# PowerSupply.net
KiCad netlist of a schematic drawn in Altium Designer
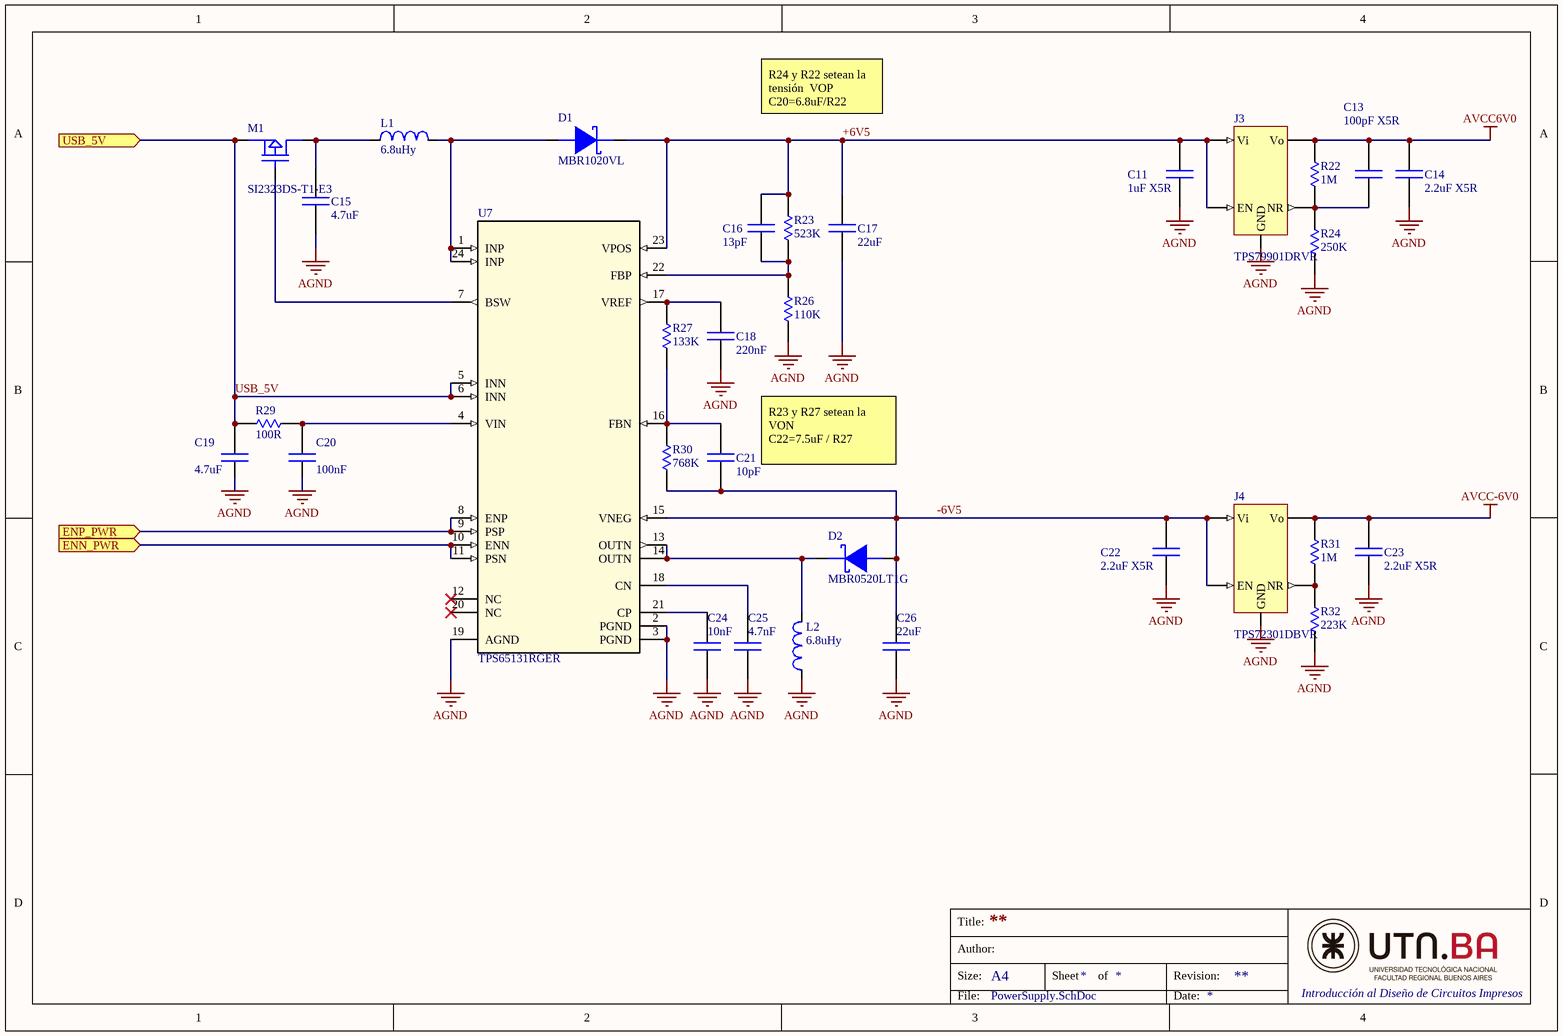
[diagram p0: PowerSupply.SchDoc]

(export (version "E")
  (design (tool "Eeschema 10.0.6"))
  (components
    (comp (ref "C11")
      (value "1uF X5R")
      (footprint "C_0805")
      (description "Capacitor")
      (libsource (lib "Gen_func") (part "Cap"))
    )
    (comp (ref "C13")
      (value "100pF X5R")
      (footprint "C_0805")
      (description "Capacitor")
      (libsource (lib "Gen_func") (part "Cap"))
    )
    (comp (ref "C14")
      (value "2.2uF X5R")
      (footprint "C_0805")
      (description "Capacitor")
      (libsource (lib "Gen_func") (part "Cap"))
    )
    (comp (ref "C15")
      (value "4.7uF")
      (footprint "C_0805")
      (description "Capacitor")
      (libsource (lib "Gen_func") (part "Cap"))
    )
    (comp (ref "C16")
      (value "13pF")
      (footprint "C_0603")
      (description "Capacitor")
      (libsource (lib "Gen_func") (part "Cap"))
    )
    (comp (ref "C17")
      (value "22uF")
      (footprint "C_1206")
      (description "Capacitor")
      (libsource (lib "Gen_func") (part "Cap"))
    )
    (comp (ref "C18")
      (value "220nF")
      (footprint "C_0603")
      (description "Capacitor")
      (libsource (lib "Gen_func") (part "Cap"))
    )
    (comp (ref "C19")
      (value "4.7uF")
      (footprint "C_0805")
      (description "Capacitor")
      (libsource (lib "Gen_func") (part "Cap"))
    )
    (comp (ref "C20")
      (value "100nF")
      (footprint "C_0603")
      (description "Capacitor")
      (libsource (lib "Gen_func") (part "Cap"))
    )
    (comp (ref "C21")
      (value "10pF")
      (footprint "C_0603")
      (description "Capacitor")
      (libsource (lib "Gen_func") (part "Cap"))
    )
    (comp (ref "C22")
      (value "2.2uF X5R")
      (footprint "C_0805")
      (description "Capacitor")
      (libsource (lib "Gen_func") (part "Cap"))
    )
    (comp (ref "C23")
      (value "2.2uF X5R")
      (footprint "C_0805")
      (description "Capacitor")
      (libsource (lib "Gen_func") (part "Cap"))
    )
    (comp (ref "C24")
      (value "10nF")
      (footprint "C_0603")
      (description "Capacitor")
      (libsource (lib "Gen_func") (part "Cap"))
    )
    (comp (ref "C25")
      (value "4.7nF")
      (footprint "C_0603")
      (description "Capacitor")
      (libsource (lib "Gen_func") (part "Cap"))
    )
    (comp (ref "C26")
      (value "22uF")
      (footprint "C_1206")
      (description "Capacitor")
      (libsource (lib "Gen_func") (part "Cap"))
    )
    (comp (ref "D1")
      (value "MBR1020VL")
      (footprint "SOD-123")
      (description "Schottky diode")
      (libsource (lib "Gen_func") (part "Diode"))
    )
    (comp (ref "D2")
      (value "MBR0520LT1G")
      (footprint "SOD-123")
      (description "Schottky diode")
      (libsource (lib "Gen_func") (part "Diode"))
    )
    (comp (ref "J3")
      (value "TPS79901DRVR")
      (footprint "WSON")
      (description "LDO_Adjustable")
      (libsource (lib "Gen_func") (part "LDO"))
    )
    (comp (ref "J4")
      (value "TPS72301DBVR")
      (footprint "SOT_23")
      (description "LDO_Adjustable")
      (libsource (lib "Gen_func") (part "LDO"))
    )
    (comp (ref "L1")
      (value "6.8uHy")
      (footprint "L_4028")
      (description "Inductor")
      (libsource (lib "Gen_func") (part "Ind"))
    )
    (comp (ref "L2")
      (value "6.8uHy")
      (footprint "L_4028")
      (description "Inductor")
      (libsource (lib "Gen_func") (part "Ind"))
    )
    (comp (ref "M1")
      (value "SI2323DS-T1-E3")
      (footprint "SOT_23_Q")
      (description "Transistor")
      (libsource (lib "Gen_func") (part "PMOS"))
    )
    (comp (ref "R22")
      (value "1M")
      (footprint "R_0603")
      (description "Resistor")
      (libsource (lib "Gen_func") (part "Res"))
    )
    (comp (ref "R23")
      (value "523K")
      (footprint "R_0603")
      (description "Resistor")
      (libsource (lib "Gen_func") (part "Res"))
    )
    (comp (ref "R24")
      (value "250K")
      (footprint "R_0603")
      (description "Resistor")
      (libsource (lib "Gen_func") (part "Res"))
    )
    (comp (ref "R26")
      (value "110K")
      (footprint "R_0603")
      (description "Resistor")
      (libsource (lib "Gen_func") (part "Res"))
    )
    (comp (ref "R27")
      (value "133K")
      (footprint "R_0603")
      (description "Resistor")
      (libsource (lib "Gen_func") (part "Res"))
    )
    (comp (ref "R29")
      (value "100R")
      (footprint "R_0603")
      (description "Resistor")
      (libsource (lib "Gen_func") (part "Res"))
    )
    (comp (ref "R30")
      (value "768K")
      (footprint "R_0603")
      (description "Resistor")
      (libsource (lib "Gen_func") (part "Res"))
    )
    (comp (ref "R31")
      (value "1M")
      (footprint "R_0603")
      (description "Resistor")
      (libsource (lib "Gen_func") (part "Res"))
    )
    (comp (ref "R32")
      (value "223K")
      (footprint "R_0603")
      (description "Resistor")
      (libsource (lib "Gen_func") (part "Res"))
    )
    (comp (ref "U7")
      (value "TPS65131RGER")
      (footprint "VQFN-N24")
      (description "Positive and Negative Output DC-DC Converter")
      (libsource (lib "Gen_func") (part "TPS65131RGER"))
    )
  )
  (nets
    (net (code "1") (name "/+6V5") (class "Default")
      (node (ref "C11") (pin "1") (pinfunction "1_1") (pintype "passive"))
      (node (ref "C16") (pin "2") (pinfunction "2_2") (pintype "passive"))
      (node (ref "C17") (pin "2") (pinfunction "2_2") (pintype "passive"))
      (node (ref "D1") (pin "1") (pinfunction "K_1") (pintype "passive"))
      (node (ref "J3") (pin "1") (pinfunction "Vi_1") (pintype "input"))
      (node (ref "J3") (pin "3") (pinfunction "EN_3") (pintype "input"))
      (node (ref "R23") (pin "1") (pinfunction "1_1") (pintype "passive"))
      (node (ref "U7") (pin "23") (pinfunction "VPOS_23") (pintype "input"))
    )
    (net (code "2") (name "/-6V5") (class "Default")
      (node (ref "C21") (pin "1") (pinfunction "1_1") (pintype "passive"))
      (node (ref "C22") (pin "1") (pinfunction "1_1") (pintype "passive"))
      (node (ref "C26") (pin "1") (pinfunction "1_1") (pintype "passive"))
      (node (ref "D2") (pin "2") (pinfunction "A_2") (pintype "passive"))
      (node (ref "J4") (pin "1") (pinfunction "Vi_1") (pintype "input"))
      (node (ref "J4") (pin "3") (pinfunction "EN_3") (pintype "input"))
      (node (ref "R30") (pin "2") (pinfunction "2_2") (pintype "passive"))
      (node (ref "U7") (pin "15") (pinfunction "VNEG_15") (pintype "input"))
    )
    (net (code "3") (name "/ENN_PWR") (class "Default")
      (node (ref "U7") (pin "10") (pinfunction "ENN_10") (pintype "input"))
      (node (ref "U7") (pin "11") (pinfunction "PSN_11") (pintype "input"))
    )
    (net (code "4") (name "/ENP_PWR") (class "Default")
      (node (ref "U7") (pin "8") (pinfunction "ENP_8") (pintype "input"))
      (node (ref "U7") (pin "9") (pinfunction "PSP_9") (pintype "input"))
    )
    (net (code "5") (name "/USB_5V") (class "Default")
      (node (ref "C19") (pin "1") (pinfunction "1_1") (pintype "passive"))
      (node (ref "M1") (pin "2") (pinfunction "Source_2") (pintype "passive"))
      (node (ref "R29") (pin "1") (pinfunction "1_1") (pintype "passive"))
      (node (ref "U7") (pin "5") (pinfunction "INN_5") (pintype "input"))
      (node (ref "U7") (pin "6") (pinfunction "INN_6") (pintype "input"))
    )
    (net (code "6") (name "AGND") (class "Default")
      (node (ref "C11") (pin "2") (pinfunction "2_2") (pintype "passive"))
      (node (ref "C14") (pin "2") (pinfunction "2_2") (pintype "passive"))
      (node (ref "C15") (pin "2") (pinfunction "2_2") (pintype "passive"))
      (node (ref "C17") (pin "1") (pinfunction "1_1") (pintype "passive"))
      (node (ref "C18") (pin "2") (pinfunction "2_2") (pintype "passive"))
      (node (ref "C19") (pin "2") (pinfunction "2_2") (pintype "passive"))
      (node (ref "C20") (pin "2") (pinfunction "2_2") (pintype "passive"))
      (node (ref "C22") (pin "2") (pinfunction "2_2") (pintype "passive"))
      (node (ref "C23") (pin "2") (pinfunction "2_2") (pintype "passive"))
      (node (ref "C24") (pin "2") (pinfunction "2_2") (pintype "passive"))
      (node (ref "C25") (pin "2") (pinfunction "2_2") (pintype "passive"))
      (node (ref "C26") (pin "2") (pinfunction "2_2") (pintype "passive"))
      (node (ref "J3") (pin "2") (pinfunction "GND_2") (pintype "power_in"))
      (node (ref "J4") (pin "2") (pinfunction "GND_2") (pintype "power_in"))
      (node (ref "L2") (pin "1") (pinfunction "1_1") (pintype "passive"))
      (node (ref "R24") (pin "1") (pinfunction "1_1") (pintype "passive"))
      (node (ref "R26") (pin "2") (pinfunction "2_2") (pintype "passive"))
      (node (ref "R32") (pin "1") (pinfunction "1_1") (pintype "passive"))
      (node (ref "U7") (pin "19") (pinfunction "AGND_19") (pintype "power_in"))
      (node (ref "U7") (pin "2") (pinfunction "PGND_2") (pintype "power_in"))
      (node (ref "U7") (pin "3") (pinfunction "PGND_3") (pintype "power_in"))
    )
    (net (code "7") (name "AVCC-6V0") (class "Default")
      (node (ref "C23") (pin "1") (pinfunction "1_1") (pintype "passive"))
      (node (ref "J4") (pin "5") (pinfunction "Vo_5") (pintype "power_in"))
      (node (ref "R31") (pin "2") (pinfunction "2_2") (pintype "passive"))
    )
    (net (code "8") (name "AVCC6V0") (class "Default")
      (node (ref "C13") (pin "1") (pinfunction "1_1") (pintype "passive"))
      (node (ref "C14") (pin "1") (pinfunction "1_1") (pintype "passive"))
      (node (ref "J3") (pin "5") (pinfunction "Vo_5") (pintype "power_in"))
      (node (ref "R22") (pin "2") (pinfunction "2_2") (pintype "passive"))
    )
    (net (code "9") (name "Net-(D1-A)") (class "Default")
      (node (ref "D1") (pin "2") (pinfunction "A_2") (pintype "passive"))
      (node (ref "L1") (pin "2") (pinfunction "2_2") (pintype "passive"))
      (node (ref "U7") (pin "1") (pinfunction "INP_1") (pintype "input"))
      (node (ref "U7") (pin "24") (pinfunction "INP_24") (pintype "input"))
    )
    (net (code "10") (name "Net-(D2-K)") (class "Default")
      (node (ref "D2") (pin "1") (pinfunction "K_1") (pintype "passive"))
      (node (ref "L2") (pin "2") (pinfunction "2_2") (pintype "passive"))
      (node (ref "U7") (pin "13") (pinfunction "OUTN_13") (pintype "output"))
      (node (ref "U7") (pin "14") (pinfunction "OUTN_14") (pintype "passive"))
    )
    (net (code "11") (name "Net-(J3-NR)") (class "Default")
      (node (ref "C13") (pin "2") (pinfunction "2_2") (pintype "passive"))
      (node (ref "J3") (pin "4") (pinfunction "NR_4") (pintype "output"))
      (node (ref "R22") (pin "1") (pinfunction "1_1") (pintype "passive"))
      (node (ref "R24") (pin "2") (pinfunction "2_2") (pintype "passive"))
    )
    (net (code "12") (name "Net-(J4-NR)") (class "Default")
      (node (ref "J4") (pin "4") (pinfunction "NR_4") (pintype "output"))
      (node (ref "R31") (pin "1") (pinfunction "1_1") (pintype "passive"))
      (node (ref "R32") (pin "2") (pinfunction "2_2") (pintype "passive"))
    )
    (net (code "13") (name "Net-(M1-Drain)") (class "Default")
      (node (ref "C15") (pin "1") (pinfunction "1_1") (pintype "passive"))
      (node (ref "L1") (pin "1") (pinfunction "1_1") (pintype "passive"))
      (node (ref "M1") (pin "3") (pinfunction "Drain_3") (pintype "passive"))
    )
    (net (code "14") (name "Net-(M1-Gate)") (class "Default")
      (node (ref "M1") (pin "1") (pinfunction "Gate_1") (pintype "passive"))
      (node (ref "U7") (pin "7") (pinfunction "BSW_7") (pintype "output"))
    )
    (net (code "15") (name "Net-(U7-CN)") (class "Default")
      (node (ref "C25") (pin "1") (pinfunction "1_1") (pintype "passive"))
      (node (ref "U7") (pin "18") (pinfunction "CN_18") (pintype "passive"))
    )
    (net (code "16") (name "Net-(U7-CP)") (class "Default")
      (node (ref "C24") (pin "1") (pinfunction "1_1") (pintype "passive"))
      (node (ref "U7") (pin "21") (pinfunction "CP_21") (pintype "passive"))
    )
    (net (code "17") (name "Net-(U7-FBN)") (class "Default")
      (node (ref "C21") (pin "2") (pinfunction "2_2") (pintype "passive"))
      (node (ref "R27") (pin "1") (pinfunction "1_1") (pintype "passive"))
      (node (ref "R30") (pin "1") (pinfunction "1_1") (pintype "passive"))
      (node (ref "U7") (pin "16") (pinfunction "FBN_16") (pintype "input"))
    )
    (net (code "18") (name "Net-(U7-FBP)") (class "Default")
      (node (ref "C16") (pin "1") (pinfunction "1_1") (pintype "passive"))
      (node (ref "R23") (pin "2") (pinfunction "2_2") (pintype "passive"))
      (node (ref "R26") (pin "1") (pinfunction "1_1") (pintype "passive"))
      (node (ref "U7") (pin "22") (pinfunction "FBP_22") (pintype "input"))
    )
    (net (code "19") (name "Net-(U7-VIN)") (class "Default")
      (node (ref "C20") (pin "1") (pinfunction "1_1") (pintype "passive"))
      (node (ref "R29") (pin "2") (pinfunction "2_2") (pintype "passive"))
      (node (ref "U7") (pin "4") (pinfunction "VIN_4") (pintype "input"))
    )
    (net (code "20") (name "Net-(U7-VREF)") (class "Default")
      (node (ref "C18") (pin "1") (pinfunction "1_1") (pintype "passive"))
      (node (ref "R27") (pin "2") (pinfunction "2_2") (pintype "passive"))
      (node (ref "U7") (pin "17") (pinfunction "VREF_17") (pintype "output"))
    )
    (net (code "21") (name "unconnected-(U7-NC-Pad12)") (class "Default")
      (node (ref "U7") (pin "12") (pinfunction "NC_12") (pintype "passive+no_connect"))
    )
    (net (code "22") (name "unconnected-(U7-NC-Pad20)") (class "Default")
      (node (ref "U7") (pin "20") (pinfunction "NC_20") (pintype "passive+no_connect"))
    )
  )
)
